# design.net
KiCad netlist of a schematic drawn in Altium Designer
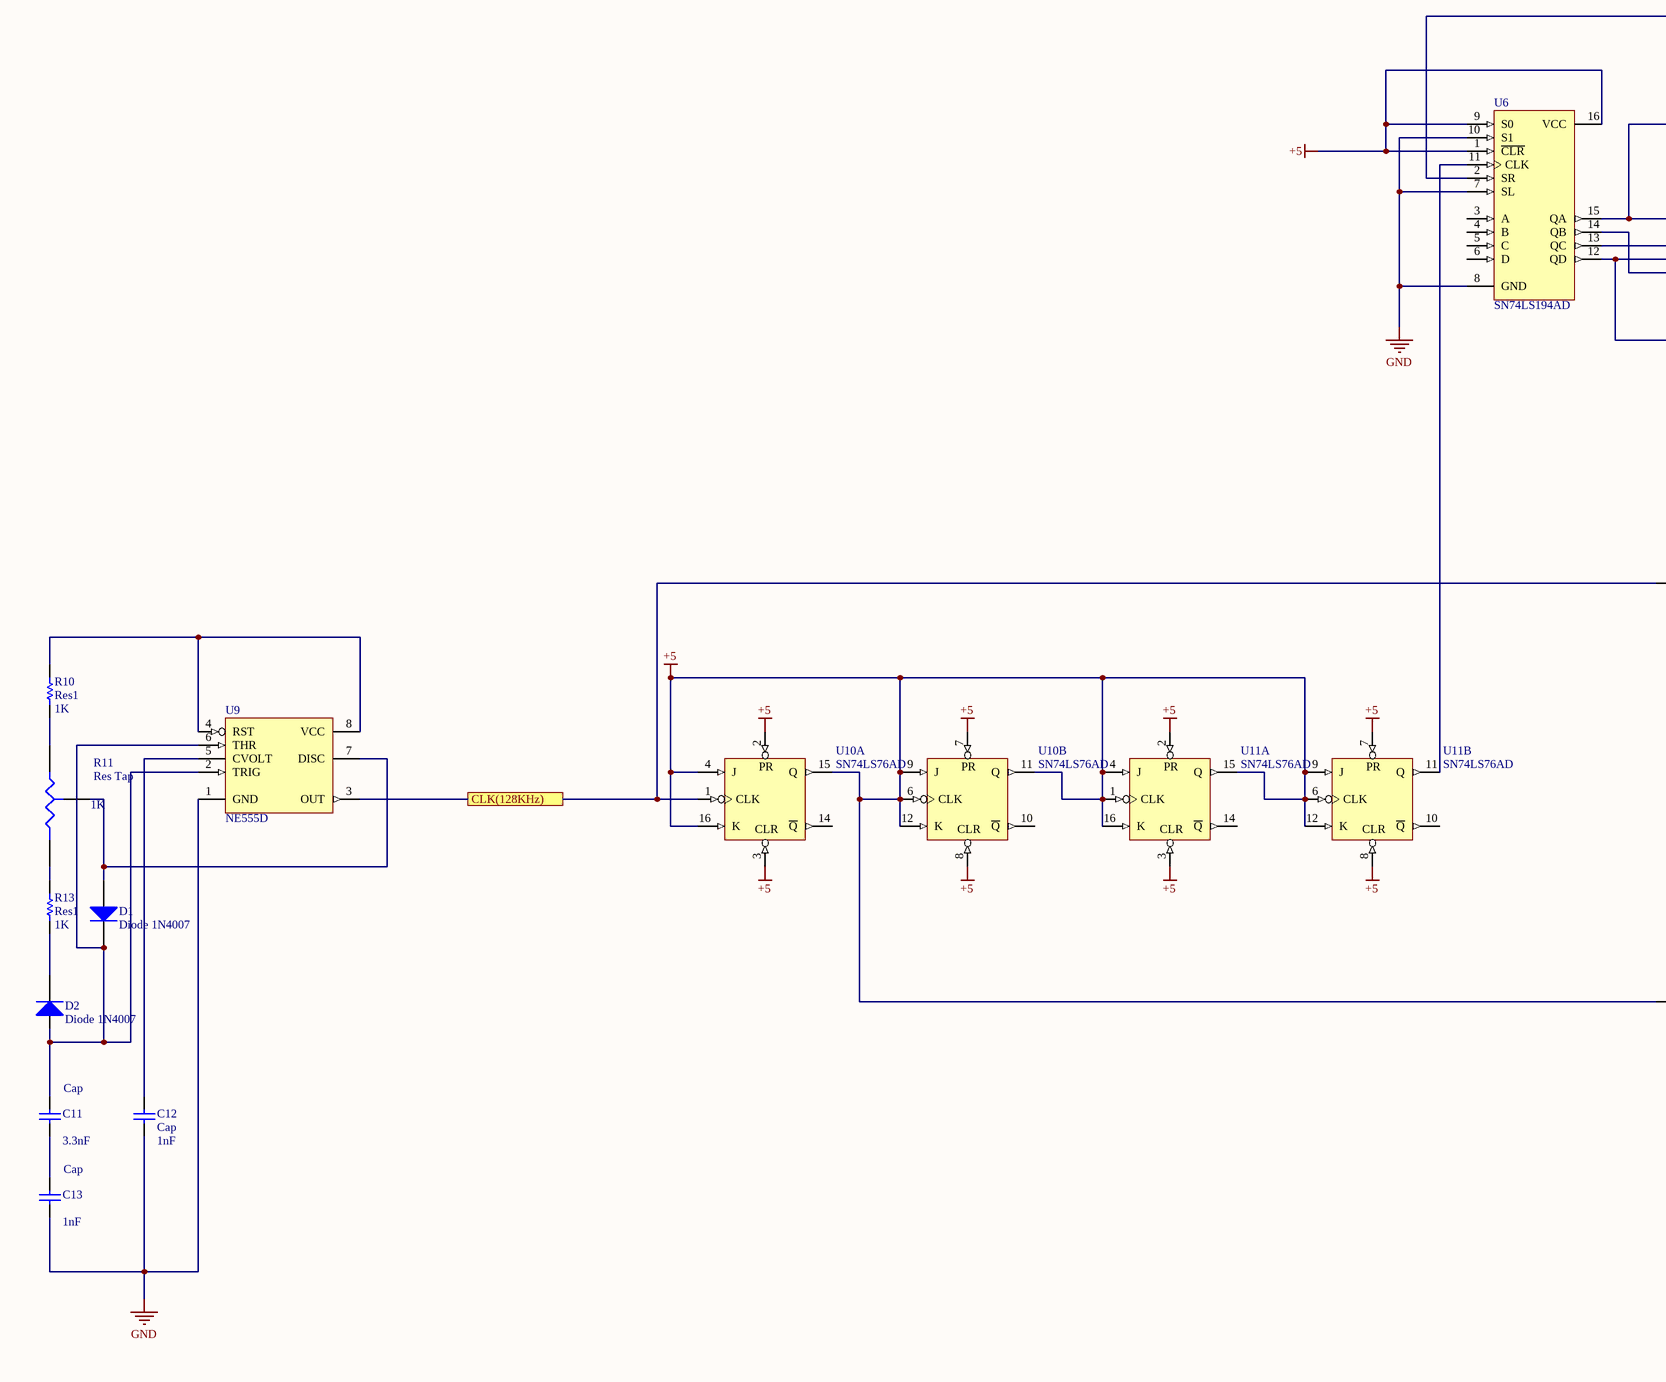
[diagram p0: 调制板原理图.SchDoc, left]
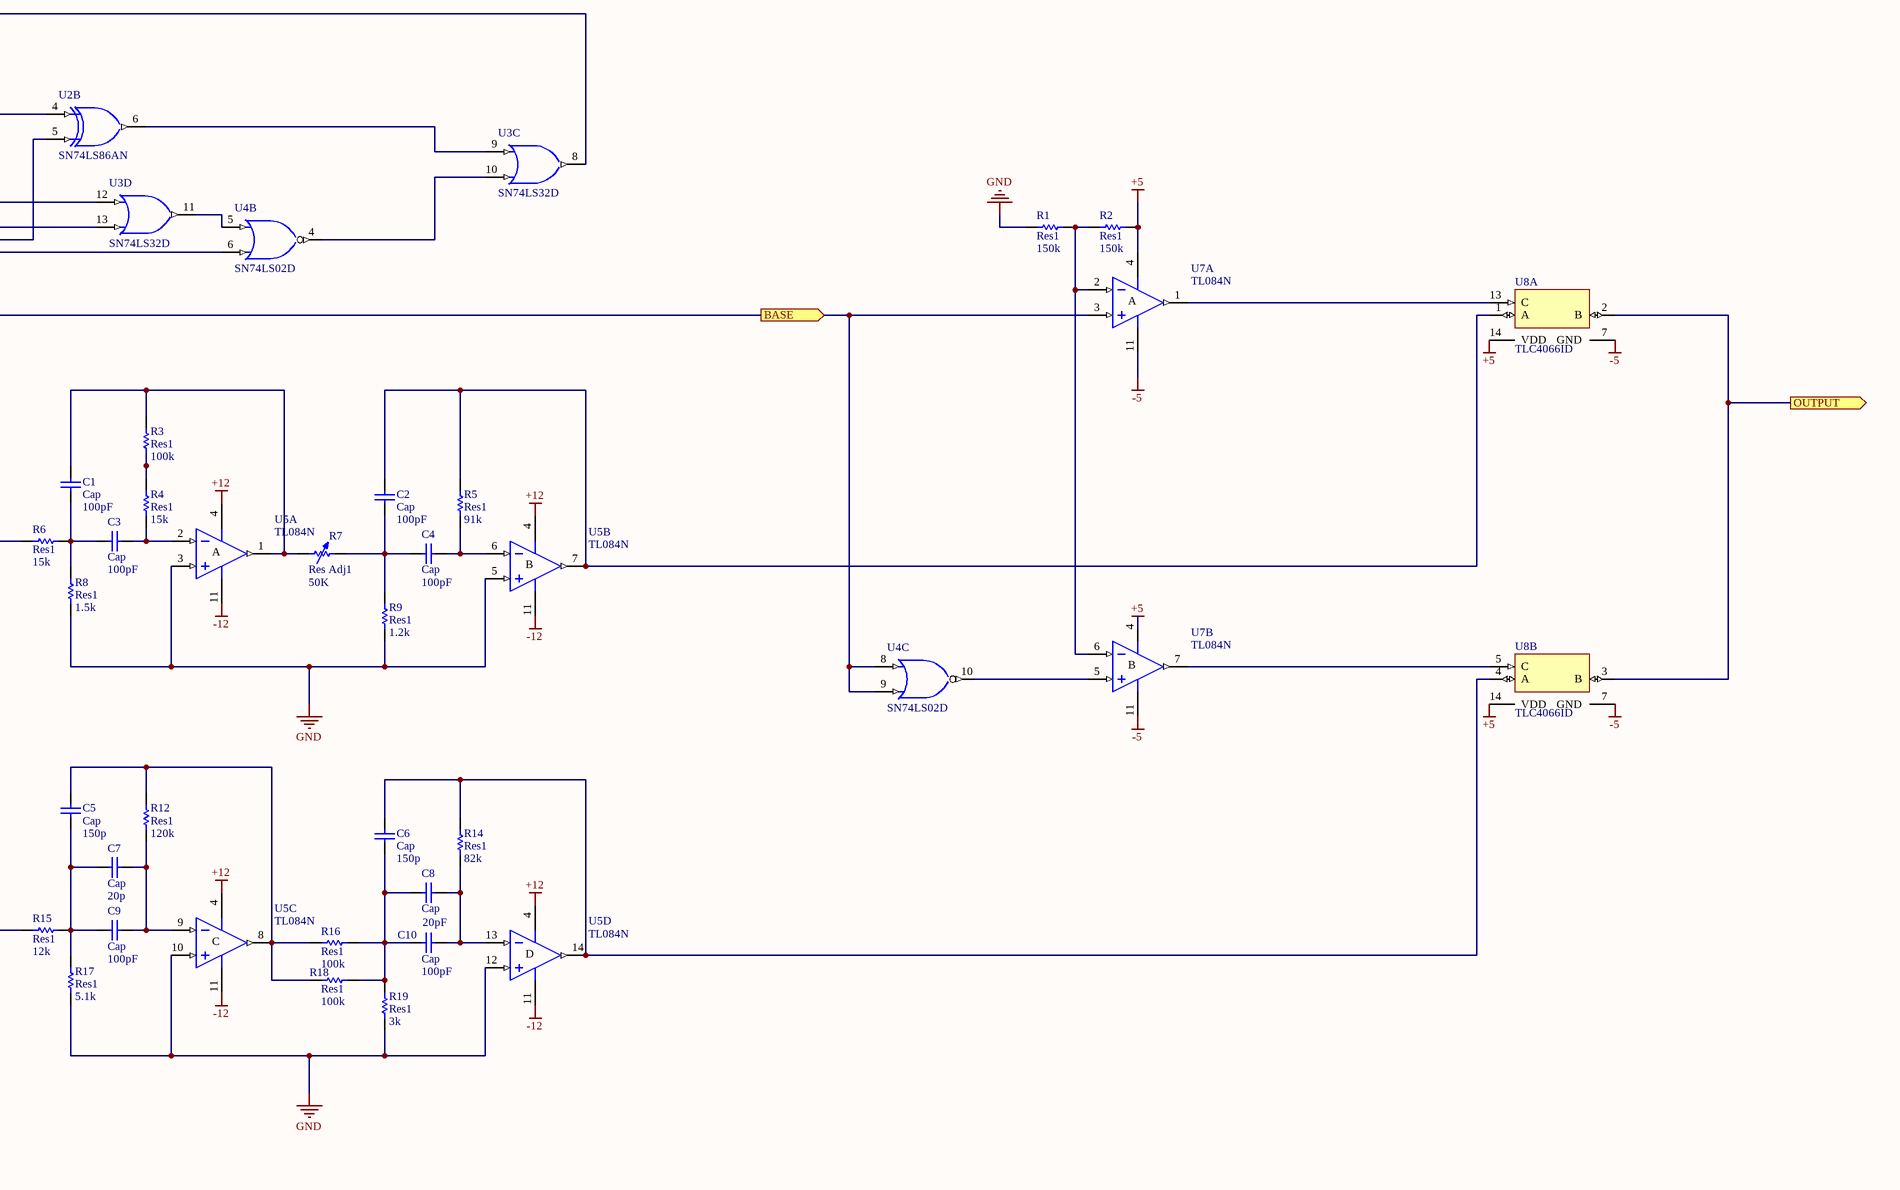
[diagram p1: 调制板原理图.SchDoc, right]

(export (version "E")
  (design (tool "Eeschema 10.0.6"))
  (components
    (comp (ref "C1")
      (value "Cap")
      (footprint "RAD-0.3")
      (description "Capacitor")
      (fields (field (name "ALTIUM_VALUE") "100pF") (field (name "PUBLISHER") "Altium Limited"))
      (libsource (lib "Miscellaneous Devices") (part "Cap"))
    )
    (comp (ref "C2")
      (value "Cap")
      (footprint "RAD-0.3")
      (description "Capacitor")
      (fields (field (name "ALTIUM_VALUE") "100pF") (field (name "PUBLISHER") "Altium Limited"))
      (libsource (lib "Miscellaneous Devices") (part "Cap"))
    )
    (comp (ref "C3")
      (value "Cap")
      (footprint "RAD-0.3")
      (description "Capacitor")
      (fields (field (name "ALTIUM_VALUE") "100pF") (field (name "PUBLISHER") "Altium Limited"))
      (libsource (lib "Miscellaneous Devices") (part "Cap"))
    )
    (comp (ref "C4")
      (value "Cap")
      (footprint "RAD-0.3")
      (description "Capacitor")
      (fields (field (name "ALTIUM_VALUE") "100pF") (field (name "PUBLISHER") "Altium Limited"))
      (libsource (lib "Miscellaneous Devices") (part "Cap"))
    )
    (comp (ref "C5")
      (value "Cap")
      (footprint "RAD-0.3")
      (description "Capacitor")
      (fields (field (name "ALTIUM_VALUE") "150p") (field (name "PUBLISHER") "Altium Limited"))
      (libsource (lib "Miscellaneous Devices") (part "Cap"))
    )
    (comp (ref "C6")
      (value "Cap")
      (footprint "RAD-0.3")
      (description "Capacitor")
      (fields (field (name "ALTIUM_VALUE") "150p") (field (name "PUBLISHER") "Altium Limited"))
      (libsource (lib "Miscellaneous Devices") (part "Cap"))
    )
    (comp (ref "C7")
      (value "Cap")
      (footprint "RAD-0.3")
      (description "Capacitor")
      (fields (field (name "ALTIUM_VALUE") "20p") (field (name "PUBLISHER") "Altium Limited"))
      (libsource (lib "Miscellaneous Devices") (part "Cap"))
    )
    (comp (ref "C8")
      (value "Cap")
      (footprint "RAD-0.3")
      (description "Capacitor")
      (fields (field (name "ALTIUM_VALUE") "20pF") (field (name "PUBLISHER") "Altium Limited"))
      (libsource (lib "Miscellaneous Devices") (part "Cap"))
    )
    (comp (ref "C9")
      (value "Cap")
      (footprint "RAD-0.3")
      (description "Capacitor")
      (fields (field (name "ALTIUM_VALUE") "100pF") (field (name "PUBLISHER") "Altium Limited"))
      (libsource (lib "Miscellaneous Devices") (part "Cap"))
    )
    (comp (ref "C10")
      (value "Cap")
      (footprint "RAD-0.3")
      (description "Capacitor")
      (fields (field (name "ALTIUM_VALUE") "100pF") (field (name "PUBLISHER") "Altium Limited"))
      (libsource (lib "Miscellaneous Devices") (part "Cap"))
    )
    (comp (ref "C11")
      (value "Cap")
      (footprint "RAD-0.3")
      (description "Capacitor")
      (fields (field (name "ALTIUM_VALUE") "3.3nF") (field (name "PUBLISHER") "Altium Limited"))
      (libsource (lib "Miscellaneous Devices") (part "Cap"))
    )
    (comp (ref "C12")
      (value "Cap")
      (footprint "RAD-0.3")
      (description "Capacitor")
      (fields (field (name "ALTIUM_VALUE") "1nF") (field (name "PUBLISHER") "Altium Limited"))
      (libsource (lib "Miscellaneous Devices") (part "Cap"))
    )
    (comp (ref "C13")
      (value "Cap")
      (footprint "RAD-0.3")
      (description "Capacitor")
      (fields (field (name "ALTIUM_VALUE") "1nF") (field (name "PUBLISHER") "Altium Limited"))
      (libsource (lib "Miscellaneous Devices") (part "Cap"))
    )
    (comp (ref "D1")
      (value "Diode 1N4007")
      (footprint "DO-41")
      (description "1 Amp General Purpose Rectifier")
      (fields (field (name "PUBLISHER") "Altium Limited"))
      (libsource (lib "Miscellaneous Devices") (part "Diode 1N4007"))
    )
    (comp (ref "D2")
      (value "Diode 1N4007")
      (footprint "DO-41")
      (description "1 Amp General Purpose Rectifier")
      (fields (field (name "PUBLISHER") "Altium Limited"))
      (libsource (lib "Miscellaneous Devices") (part "Diode 1N4007"))
    )
    (comp (ref "R1")
      (value "Res1")
      (footprint "AXIAL-0.3")
      (description "Resistor")
      (fields (field (name "ALTIUM_VALUE") "150k") (field (name "PUBLISHER") "Altium Limited"))
      (libsource (lib "Miscellaneous Devices") (part "Res1"))
    )
    (comp (ref "R2")
      (value "Res1")
      (footprint "AXIAL-0.3")
      (description "Resistor")
      (fields (field (name "ALTIUM_VALUE") "150k") (field (name "PUBLISHER") "Altium Limited"))
      (libsource (lib "Miscellaneous Devices") (part "Res1"))
    )
    (comp (ref "R3")
      (value "Res1")
      (footprint "AXIAL-0.3")
      (description "Resistor")
      (fields (field (name "ALTIUM_VALUE") "100k") (field (name "PUBLISHER") "Altium Limited"))
      (libsource (lib "Miscellaneous Devices") (part "Res1"))
    )
    (comp (ref "R4")
      (value "Res1")
      (footprint "AXIAL-0.3")
      (description "Resistor")
      (fields (field (name "ALTIUM_VALUE") "15k") (field (name "PUBLISHER") "Altium Limited"))
      (libsource (lib "Miscellaneous Devices") (part "Res1"))
    )
    (comp (ref "R5")
      (value "Res1")
      (footprint "AXIAL-0.3")
      (description "Resistor")
      (fields (field (name "ALTIUM_VALUE") "91k") (field (name "PUBLISHER") "Altium Limited"))
      (libsource (lib "Miscellaneous Devices") (part "Res1"))
    )
    (comp (ref "R6")
      (value "Res1")
      (footprint "AXIAL-0.3")
      (description "Resistor")
      (fields (field (name "ALTIUM_VALUE") "15k") (field (name "PUBLISHER") "Altium Limited"))
      (libsource (lib "Miscellaneous Devices") (part "Res1"))
    )
    (comp (ref "R7")
      (value "Res Adj1")
      (footprint "AXIAL-0.7")
      (description "Variable Resistor")
      (fields (field (name "ALTIUM_VALUE") "50K") (field (name "PUBLISHER") "Altium Limited"))
      (libsource (lib "Miscellaneous Devices") (part "Res Adj1"))
    )
    (comp (ref "R8")
      (value "Res1")
      (footprint "AXIAL-0.3")
      (description "Resistor")
      (fields (field (name "ALTIUM_VALUE") "1.5k") (field (name "PUBLISHER") "Altium Limited"))
      (libsource (lib "Miscellaneous Devices") (part "Res1"))
    )
    (comp (ref "R9")
      (value "Res1")
      (footprint "AXIAL-0.3")
      (description "Resistor")
      (fields (field (name "ALTIUM_VALUE") "1.2k") (field (name "PUBLISHER") "Altium Limited"))
      (libsource (lib "Miscellaneous Devices") (part "Res1"))
    )
    (comp (ref "R10")
      (value "Res1")
      (footprint "AXIAL-0.3")
      (description "Resistor")
      (fields (field (name "ALTIUM_VALUE") "1K") (field (name "PUBLISHER") "Altium Limited"))
      (libsource (lib "Miscellaneous Devices") (part "Res1"))
    )
    (comp (ref "R11")
      (value "Res Tap")
      (footprint "VR3")
      (description "Tapped Resistor")
      (fields (field (name "ALTIUM_VALUE") "1K") (field (name "PUBLISHER") "Altium Limited"))
      (libsource (lib "Miscellaneous Devices") (part "Res Tap"))
    )
    (comp (ref "R12")
      (value "Res1")
      (footprint "AXIAL-0.3")
      (description "Resistor")
      (fields (field (name "ALTIUM_VALUE") "120k") (field (name "PUBLISHER") "Altium Limited"))
      (libsource (lib "Miscellaneous Devices") (part "Res1"))
    )
    (comp (ref "R13")
      (value "Res1")
      (footprint "AXIAL-0.3")
      (description "Resistor")
      (fields (field (name "ALTIUM_VALUE") "1K") (field (name "PUBLISHER") "Altium Limited"))
      (libsource (lib "Miscellaneous Devices") (part "Res1"))
    )
    (comp (ref "R14")
      (value "Res1")
      (footprint "AXIAL-0.3")
      (description "Resistor")
      (fields (field (name "ALTIUM_VALUE") "82k") (field (name "PUBLISHER") "Altium Limited"))
      (libsource (lib "Miscellaneous Devices") (part "Res1"))
    )
    (comp (ref "R15")
      (value "Res1")
      (footprint "AXIAL-0.3")
      (description "Resistor")
      (fields (field (name "ALTIUM_VALUE") "12k") (field (name "PUBLISHER") "Altium Limited"))
      (libsource (lib "Miscellaneous Devices") (part "Res1"))
    )
    (comp (ref "R16")
      (value "Res1")
      (footprint "AXIAL-0.3")
      (description "Resistor")
      (fields (field (name "ALTIUM_VALUE") "100k") (field (name "PUBLISHER") "Altium Limited"))
      (libsource (lib "Miscellaneous Devices") (part "Res1"))
    )
    (comp (ref "R17")
      (value "Res1")
      (footprint "AXIAL-0.3")
      (description "Resistor")
      (fields (field (name "ALTIUM_VALUE") "5.1k") (field (name "PUBLISHER") "Altium Limited"))
      (libsource (lib "Miscellaneous Devices") (part "Res1"))
    )
    (comp (ref "R18")
      (value "Res1")
      (footprint "AXIAL-0.3")
      (description "Resistor")
      (fields (field (name "ALTIUM_VALUE") "100k") (field (name "PUBLISHER") "Altium Limited"))
      (libsource (lib "Miscellaneous Devices") (part "Res1"))
    )
    (comp (ref "R19")
      (value "Res1")
      (footprint "AXIAL-0.3")
      (description "Resistor")
      (fields (field (name "ALTIUM_VALUE") "3k") (field (name "PUBLISHER") "Altium Limited"))
      (libsource (lib "Miscellaneous Devices") (part "Res1"))
    )
    (comp (ref "U2")
      (value "SN74LS86AN")
      (footprint "N014")
      (description "Quadruple 2-Input Exclusive-OR Gate")
      (fields (field (name "PUBLISHER") "Altium Limited"))
      (libsource (lib "TI Logic Gate 2") (part "SN74LS86AN"))
    )
    (comp (ref "U3")
      (value "SN74LS32D")
      (footprint "D014_L")
      (description "Quadruple 2-Input Positive-OR Gate")
      (fields (field (name "PUBLISHER") "Altium Limited"))
      (libsource (lib "TI Logic Gate 2") (part "SN74LS32D"))
    )
    (comp (ref "U4")
      (value "SN74LS02D")
      (footprint "D014_L")
      (description "Quadruple 2-Input Positive-NOR Gate")
      (fields (field (name "PUBLISHER") "Altium Limited"))
      (libsource (lib "TI Logic Gate 2") (part "SN74LS02D"))
    )
    (comp (ref "U5")
      (value "TL084N")
      (footprint "N014")
      (description "JFET-Input Operational Amplifier")
      (fields (field (name "PUBLISHER") "Altium Limited"))
      (libsource (lib "TI Operational Amplifier") (part "TL084N"))
    )
    (comp (ref "U6")
      (value "SN74LS194AD")
      (footprint "D016_L")
      (description "4-Bit Bidirectional Universal Shift Register")
      (fields (field (name "PUBLISHER") "Altium Limited"))
      (libsource (lib "TI Logic Register") (part "SN74LS194AD"))
    )
    (comp (ref "U7")
      (value "TL084N")
      (footprint "N014")
      (description "JFET-Input Operational Amplifier")
      (fields (field (name "PUBLISHER") "Altium Limited"))
      (libsource (lib "TI Operational Amplifier") (part "TL084N"))
    )
    (comp (ref "U8")
      (value "TLC4066ID")
      (footprint "D014_L")
      (description "Quadruple Bilateral Analog Switch")
      (fields (field (name "PUBLISHER") "Altium Limited"))
      (libsource (lib "altium-import") (part "root_0_TLC4066ID_"))
    )
    (comp (ref "U9")
      (value "NE555D")
      (footprint "D008_L")
      (description "Precision Timer")
      (fields (field (name "PUBLISHER") "Altium Limited"))
      (libsource (lib "TI Analog Timer Circuit") (part "NE555D"))
    )
    (comp (ref "U10")
      (value "SN74LS76AD")
      (footprint "D016_L")
      (description "Dual J-K Flip-Flop with Preset and Clear")
      (fields (field (name "PUBLISHER") "Altium Limited"))
      (libsource (lib "TI Logic Flip-Flop") (part "SN74LS76AD"))
    )
    (comp (ref "U11")
      (value "SN74LS76AD")
      (footprint "D016_L")
      (description "Dual J-K Flip-Flop with Preset and Clear")
      (fields (field (name "PUBLISHER") "Altium Limited"))
      (libsource (lib "TI Logic Flip-Flop") (part "SN74LS76AD"))
    )
  )
  (nets
    (net (code "1") (name "+5") (class "Default")
      (node (ref "R15") (pin "1") (pinfunction "1_1") (pintype "passive"))
      (node (ref "R2") (pin "2") (pinfunction "2_2") (pintype "passive"))
      (node (ref "U10") (pin "11") (pinfunction "Q_11") (pintype "output"))
      (node (ref "U10") (pin "12") (pinfunction "K_12") (pintype "input"))
      (node (ref "U10") (pin "15") (pinfunction "Q_15") (pintype "output"))
      (node (ref "U10") (pin "16") (pinfunction "K_16") (pintype "input"))
      (node (ref "U10") (pin "2") (pinfunction "PR_2") (pintype "input"))
      (node (ref "U10") (pin "3") (pinfunction "CLR_3") (pintype "input"))
      (node (ref "U10") (pin "4") (pinfunction "J_4") (pintype "input"))
      (node (ref "U10") (pin "6") (pinfunction "CLK_6") (pintype "input"))
      (node (ref "U10") (pin "7") (pinfunction "PR_7") (pintype "input"))
      (node (ref "U10") (pin "8") (pinfunction "CLR_8") (pintype "input"))
      (node (ref "U10") (pin "9") (pinfunction "J_9") (pintype "input"))
      (node (ref "U11") (pin "1") (pinfunction "CLK_1") (pintype "input"))
      (node (ref "U11") (pin "12") (pinfunction "K_12") (pintype "input"))
      (node (ref "U11") (pin "15") (pinfunction "Q_15") (pintype "output"))
      (node (ref "U11") (pin "16") (pinfunction "K_16") (pintype "input"))
      (node (ref "U11") (pin "2") (pinfunction "PR_2") (pintype "input"))
      (node (ref "U11") (pin "3") (pinfunction "CLR_3") (pintype "input"))
      (node (ref "U11") (pin "4") (pinfunction "J_4") (pintype "input"))
      (node (ref "U11") (pin "6") (pinfunction "CLK_6") (pintype "input"))
      (node (ref "U11") (pin "7") (pinfunction "PR_7") (pintype "input"))
      (node (ref "U11") (pin "8") (pinfunction "CLR_8") (pintype "input"))
      (node (ref "U11") (pin "9") (pinfunction "J_9") (pintype "input"))
      (node (ref "U6") (pin "1") (pinfunction "~{CLR}_1") (pintype "input"))
      (node (ref "U6") (pin "16") (pinfunction "VCC_16") (pintype "power_in"))
      (node (ref "U6") (pin "9") (pinfunction "S0_9") (pintype "input"))
      (node (ref "U7") (pin "4") (pinfunction "V+_4") (pintype "power_in"))
      (node (ref "U8") (pin "14") (pinfunction "VDD_14") (pintype "power_in"))
    )
    (net (code "2") (name "+12") (class "Default")
      (node (ref "U5") (pin "4") (pinfunction "V+_4") (pintype "power_in"))
    )
    (net (code "3") (name "-5") (class "Default")
      (node (ref "C12") (pin "1") (pinfunction "1_1") (pintype "passive"))
      (node (ref "C13") (pin "1") (pinfunction "1_1") (pintype "passive"))
      (node (ref "R1") (pin "1") (pinfunction "1_1") (pintype "passive"))
      (node (ref "R17") (pin "1") (pinfunction "1_1") (pintype "passive"))
      (node (ref "R19") (pin "1") (pinfunction "1_1") (pintype "passive"))
      (node (ref "R8") (pin "1") (pinfunction "1_1") (pintype "passive"))
      (node (ref "R9") (pin "1") (pinfunction "1_1") (pintype "passive"))
      (node (ref "U10") (pin "13") (pinfunction "GND_13") (pintype "power_in"))
      (node (ref "U11") (pin "13") (pinfunction "GND_13") (pintype "power_in"))
      (node (ref "U2") (pin "7") (pinfunction "GND_7") (pintype "power_in"))
      (node (ref "U3") (pin "7") (pinfunction "GND_7") (pintype "power_in"))
      (node (ref "U4") (pin "7") (pinfunction "GND_7") (pintype "power_in"))
      (node (ref "U5") (pin "10") (pinfunction "IN+_10") (pintype "input"))
      (node (ref "U5") (pin "12") (pinfunction "IN+_12") (pintype "input"))
      (node (ref "U5") (pin "3") (pinfunction "IN+_3") (pintype "input"))
      (node (ref "U5") (pin "5") (pinfunction "IN+_5") (pintype "input"))
      (node (ref "U6") (pin "10") (pinfunction "S1_10") (pintype "input"))
      (node (ref "U6") (pin "7") (pinfunction "SL_7") (pintype "input"))
      (node (ref "U6") (pin "8") (pinfunction "GND_8") (pintype "power_in"))
      (node (ref "U7") (pin "11") (pinfunction "V-_11") (pintype "power_in"))
      (node (ref "U8") (pin "7") (pinfunction "GND_7") (pintype "power_in"))
      (node (ref "U9") (pin "1") (pinfunction "GND_1") (pintype "power_in"))
    )
    (net (code "4") (name "-12") (class "Default")
      (node (ref "U5") (pin "11") (pinfunction "V-_11") (pintype "power_in"))
    )
    (net (code "5") (name "/BASE") (class "Default")
      (node (ref "U2") (pin "5") (pinfunction "B_5") (pintype "input"))
      (node (ref "U4") (pin "8") (pinfunction "A_8") (pintype "input"))
      (node (ref "U4") (pin "9") (pinfunction "B_9") (pintype "input"))
      (node (ref "U6") (pin "12") (pinfunction "QD_12") (pintype "output"))
      (node (ref "U7") (pin "3") (pinfunction "IN+_3") (pintype "input"))
    )
    (net (code "6") (name "/CLK(128KHz)") (class "Default")
      (node (ref "R6") (pin "1") (pinfunction "1_1") (pintype "passive"))
      (node (ref "U10") (pin "1") (pinfunction "CLK_1") (pintype "input"))
      (node (ref "U9") (pin "3") (pinfunction "OUT_3") (pintype "output"))
    )
    (net (code "7") (name "/OUTPUT") (class "Default")
      (node (ref "U8") (pin "2") (pinfunction "B_2") (pintype "bidirectional"))
      (node (ref "U8") (pin "3") (pinfunction "B_3") (pintype "bidirectional"))
    )
    (net (code "8") (name "Net-(C1-Pad1)") (class "Default")
      (node (ref "C1") (pin "1") (pinfunction "1_1") (pintype "passive"))
      (node (ref "C3") (pin "1") (pinfunction "1_1") (pintype "passive"))
      (node (ref "R6") (pin "2") (pinfunction "2_2") (pintype "passive"))
      (node (ref "R8") (pin "2") (pinfunction "2_2") (pintype "passive"))
    )
    (net (code "9") (name "Net-(C2-Pad1)") (class "Default")
      (node (ref "C2") (pin "1") (pinfunction "1_1") (pintype "passive"))
      (node (ref "C4") (pin "1") (pinfunction "1_1") (pintype "passive"))
      (node (ref "R7") (pin "2") (pinfunction "2_2") (pintype "passive"))
      (node (ref "R9") (pin "2") (pinfunction "2_2") (pintype "passive"))
    )
    (net (code "10") (name "Net-(C5-Pad1)") (class "Default")
      (node (ref "C5") (pin "1") (pinfunction "1_1") (pintype "passive"))
      (node (ref "C7") (pin "1") (pinfunction "1_1") (pintype "passive"))
      (node (ref "C9") (pin "1") (pinfunction "1_1") (pintype "passive"))
      (node (ref "R15") (pin "2") (pinfunction "2_2") (pintype "passive"))
      (node (ref "R17") (pin "2") (pinfunction "2_2") (pintype "passive"))
    )
    (net (code "11") (name "Net-(C10-Pad1)") (class "Default")
      (node (ref "C10") (pin "1") (pinfunction "1_1") (pintype "passive"))
      (node (ref "C6") (pin "1") (pinfunction "1_1") (pintype "passive"))
      (node (ref "C8") (pin "1") (pinfunction "1_1") (pintype "passive"))
      (node (ref "R16") (pin "2") (pinfunction "2_2") (pintype "passive"))
      (node (ref "R18") (pin "2") (pinfunction "2_2") (pintype "passive"))
      (node (ref "R19") (pin "2") (pinfunction "2_2") (pintype "passive"))
    )
    (net (code "12") (name "Net-(C11-Pad1)") (class "Default")
      (node (ref "C11") (pin "1") (pinfunction "1_1") (pintype "passive"))
      (node (ref "C13") (pin "2") (pinfunction "2_2") (pintype "passive"))
    )
    (net (code "13") (name "Net-(D1-A)") (class "Default")
      (node (ref "D1") (pin "1") (pinfunction "A_1") (pintype "passive"))
      (node (ref "R11") (pin "3") (pinfunction "TAP_3") (pintype "passive"))
      (node (ref "U9") (pin "7") (pinfunction "DISC_7") (pintype "open_collector"))
    )
    (net (code "14") (name "Net-(D1-K)") (class "Default")
      (node (ref "C11") (pin "2") (pinfunction "2_2") (pintype "passive"))
      (node (ref "D1") (pin "2") (pinfunction "K_2") (pintype "passive"))
      (node (ref "D2") (pin "1") (pinfunction "A_1") (pintype "passive"))
      (node (ref "U9") (pin "2") (pinfunction "TRIG_2") (pintype "input"))
      (node (ref "U9") (pin "6") (pinfunction "THR_6") (pintype "input"))
    )
    (net (code "15") (name "Net-(D2-K)") (class "Default")
      (node (ref "D2") (pin "2") (pinfunction "K_2") (pintype "passive"))
      (node (ref "R13") (pin "1") (pinfunction "1_1") (pintype "passive"))
    )
    (net (code "16") (name "Net-(R3-Pad1)") (class "Default")
      (node (ref "R3") (pin "1") (pinfunction "1_1") (pintype "passive"))
      (node (ref "R4") (pin "2") (pinfunction "2_2") (pintype "passive"))
    )
    (net (code "17") (name "Net-(R11-A)") (class "Default")
      (node (ref "R10") (pin "1") (pinfunction "1_1") (pintype "passive"))
      (node (ref "R11") (pin "1") (pinfunction "A_1") (pintype "passive"))
    )
    (net (code "18") (name "Net-(R11-B)") (class "Default")
      (node (ref "R11") (pin "2") (pinfunction "B_2") (pintype "passive"))
      (node (ref "R13") (pin "2") (pinfunction "2_2") (pintype "passive"))
    )
    (net (code "19") (name "Net-(U2B-A)") (class "Default")
      (node (ref "U2") (pin "4") (pinfunction "A_4") (pintype "input"))
      (node (ref "U3") (pin "12") (pinfunction "A_12") (pintype "input"))
      (node (ref "U6") (pin "15") (pinfunction "QA_15") (pintype "output"))
    )
    (net (code "20") (name "Net-(U2B-Y)") (class "Default")
      (node (ref "U2") (pin "6") (pinfunction "Y_6") (pintype "output"))
      (node (ref "U3") (pin "9") (pinfunction "A_9") (pintype "input"))
    )
    (net (code "21") (name "Net-(U3C-B)") (class "Default")
      (node (ref "U3") (pin "10") (pinfunction "B_10") (pintype "input"))
      (node (ref "U4") (pin "4") (pinfunction "Y_4") (pintype "output"))
    )
    (net (code "22") (name "Net-(U3C-Y)") (class "Default")
      (node (ref "U3") (pin "8") (pinfunction "Y_8") (pintype "output"))
      (node (ref "U6") (pin "2") (pinfunction "SR_2") (pintype "input"))
    )
    (net (code "23") (name "Net-(U3D-B)") (class "Default")
      (node (ref "U3") (pin "13") (pinfunction "B_13") (pintype "input"))
      (node (ref "U6") (pin "13") (pinfunction "QC_13") (pintype "output"))
    )
    (net (code "24") (name "Net-(U3D-Y)") (class "Default")
      (node (ref "U3") (pin "11") (pinfunction "Y_11") (pintype "output"))
      (node (ref "U4") (pin "5") (pinfunction "A_5") (pintype "input"))
    )
    (net (code "25") (name "Net-(U4B-B)") (class "Default")
      (node (ref "U4") (pin "6") (pinfunction "B_6") (pintype "input"))
      (node (ref "U6") (pin "14") (pinfunction "QB_14") (pintype "output"))
    )
    (net (code "26") (name "Net-(U4C-Y)") (class "Default")
      (node (ref "U4") (pin "10") (pinfunction "Y_10") (pintype "output"))
      (node (ref "U7") (pin "5") (pinfunction "IN+_5") (pintype "input"))
    )
    (net (code "27") (name "Net-(U5A-IN-)") (class "Default")
      (node (ref "C3") (pin "2") (pinfunction "2_2") (pintype "passive"))
      (node (ref "R4") (pin "1") (pinfunction "1_1") (pintype "passive"))
      (node (ref "U5") (pin "2") (pinfunction "IN-_2") (pintype "input"))
    )
    (net (code "28") (name "Net-(U5A-OUT)") (class "Default")
      (node (ref "C1") (pin "2") (pinfunction "2_2") (pintype "passive"))
      (node (ref "R3") (pin "2") (pinfunction "2_2") (pintype "passive"))
      (node (ref "R7") (pin "1") (pinfunction "1_1") (pintype "passive"))
      (node (ref "U5") (pin "1") (pinfunction "OUT_1") (pintype "output"))
    )
    (net (code "29") (name "Net-(U5B-IN-)") (class "Default")
      (node (ref "C4") (pin "2") (pinfunction "2_2") (pintype "passive"))
      (node (ref "R5") (pin "1") (pinfunction "1_1") (pintype "passive"))
      (node (ref "U5") (pin "6") (pinfunction "IN-_6") (pintype "input"))
    )
    (net (code "30") (name "Net-(U5B-OUT)") (class "Default")
      (node (ref "C2") (pin "2") (pinfunction "2_2") (pintype "passive"))
      (node (ref "R5") (pin "2") (pinfunction "2_2") (pintype "passive"))
      (node (ref "U5") (pin "7") (pinfunction "OUT_7") (pintype "output"))
      (node (ref "U8") (pin "1") (pinfunction "A_1") (pintype "bidirectional"))
    )
    (net (code "31") (name "Net-(U5C-IN-)") (class "Default")
      (node (ref "C7") (pin "2") (pinfunction "2_2") (pintype "passive"))
      (node (ref "C9") (pin "2") (pinfunction "2_2") (pintype "passive"))
      (node (ref "R12") (pin "1") (pinfunction "1_1") (pintype "passive"))
      (node (ref "U5") (pin "9") (pinfunction "IN-_9") (pintype "input"))
    )
    (net (code "32") (name "Net-(U5C-OUT)") (class "Default")
      (node (ref "C5") (pin "2") (pinfunction "2_2") (pintype "passive"))
      (node (ref "R12") (pin "2") (pinfunction "2_2") (pintype "passive"))
      (node (ref "R16") (pin "1") (pinfunction "1_1") (pintype "passive"))
      (node (ref "R18") (pin "1") (pinfunction "1_1") (pintype "passive"))
      (node (ref "U5") (pin "8") (pinfunction "OUT_8") (pintype "output"))
    )
    (net (code "33") (name "Net-(U5D-IN-)") (class "Default")
      (node (ref "C10") (pin "2") (pinfunction "2_2") (pintype "passive"))
      (node (ref "C8") (pin "2") (pinfunction "2_2") (pintype "passive"))
      (node (ref "R14") (pin "1") (pinfunction "1_1") (pintype "passive"))
      (node (ref "U5") (pin "13") (pinfunction "IN-_13") (pintype "input"))
    )
    (net (code "34") (name "Net-(U5D-OUT)") (class "Default")
      (node (ref "C6") (pin "2") (pinfunction "2_2") (pintype "passive"))
      (node (ref "R14") (pin "2") (pinfunction "2_2") (pintype "passive"))
      (node (ref "U5") (pin "14") (pinfunction "OUT_14") (pintype "output"))
      (node (ref "U8") (pin "4") (pinfunction "A_4") (pintype "bidirectional"))
    )
    (net (code "35") (name "Net-(U7A-IN-)") (class "Default")
      (node (ref "R1") (pin "2") (pinfunction "2_2") (pintype "passive"))
      (node (ref "R2") (pin "1") (pinfunction "1_1") (pintype "passive"))
      (node (ref "U7") (pin "2") (pinfunction "IN-_2") (pintype "input"))
      (node (ref "U7") (pin "6") (pinfunction "IN-_6") (pintype "input"))
    )
    (net (code "36") (name "Net-(U7A-OUT)") (class "Default")
      (node (ref "U7") (pin "1") (pinfunction "OUT_1") (pintype "output"))
      (node (ref "U8") (pin "13") (pinfunction "C_13") (pintype "input"))
    )
    (net (code "37") (name "Net-(U7B-OUT)") (class "Default")
      (node (ref "U7") (pin "7") (pinfunction "OUT_7") (pintype "output"))
      (node (ref "U8") (pin "5") (pinfunction "C_5") (pintype "input"))
    )
    (net (code "38") (name "Net-(U9-CVOLT)") (class "Default")
      (node (ref "C12") (pin "2") (pinfunction "2_2") (pintype "passive"))
      (node (ref "U9") (pin "5") (pinfunction "CVOLT_5") (pintype "passive"))
    )
    (net (code "39") (name "Net-(U9-RST)") (class "Default")
      (node (ref "R10") (pin "2") (pinfunction "2_2") (pintype "passive"))
      (node (ref "U9") (pin "4") (pinfunction "RST_4") (pintype "input"))
      (node (ref "U9") (pin "8") (pinfunction "VCC_8") (pintype "power_in"))
    )
    (net (code "40") (name "Net-(U11B-Q)") (class "Default")
      (node (ref "U11") (pin "11") (pinfunction "Q_11") (pintype "output"))
      (node (ref "U6") (pin "11") (pinfunction "CLK_11") (pintype "input"))
    )
    (net (code "41") (name "VCC") (class "Default")
      (node (ref "U10") (pin "5") (pinfunction "VCC_5") (pintype "power_in"))
      (node (ref "U11") (pin "5") (pinfunction "VCC_5") (pintype "power_in"))
      (node (ref "U2") (pin "14") (pinfunction "VCC_14") (pintype "power_in"))
      (node (ref "U3") (pin "14") (pinfunction "VCC_14") (pintype "power_in"))
      (node (ref "U4") (pin "14") (pinfunction "VCC_14") (pintype "power_in"))
    )
    (net (code "42") (name "unconnected-(U6-A-Pad3)") (class "Default")
      (node (ref "U6") (pin "3") (pinfunction "A_3") (pintype "input"))
    )
    (net (code "43") (name "unconnected-(U6-B-Pad4)") (class "Default")
      (node (ref "U6") (pin "4") (pinfunction "B_4") (pintype "input"))
    )
    (net (code "44") (name "unconnected-(U6-C-Pad5)") (class "Default")
      (node (ref "U6") (pin "5") (pinfunction "C_5") (pintype "input"))
    )
    (net (code "45") (name "unconnected-(U6-D-Pad6)") (class "Default")
      (node (ref "U6") (pin "6") (pinfunction "D_6") (pintype "input"))
    )
    (net (code "46") (name "unconnected-(U10A-~{Q}-Pad14)") (class "Default")
      (node (ref "U10") (pin "14") (pinfunction "~{Q}_14") (pintype "output"))
    )
    (net (code "47") (name "unconnected-(U10B-~{Q}-Pad10)") (class "Default")
      (node (ref "U10") (pin "10") (pinfunction "~{Q}_10") (pintype "output"))
    )
    (net (code "48") (name "unconnected-(U11A-~{Q}-Pad14)") (class "Default")
      (node (ref "U11") (pin "14") (pinfunction "~{Q}_14") (pintype "output"))
    )
    (net (code "49") (name "unconnected-(U11B-~{Q}-Pad10)") (class "Default")
      (node (ref "U11") (pin "10") (pinfunction "~{Q}_10") (pintype "output"))
    )
  )
)
